# PediLEDStrip.net
KiCad netlist of a schematic drawn in EAGLE
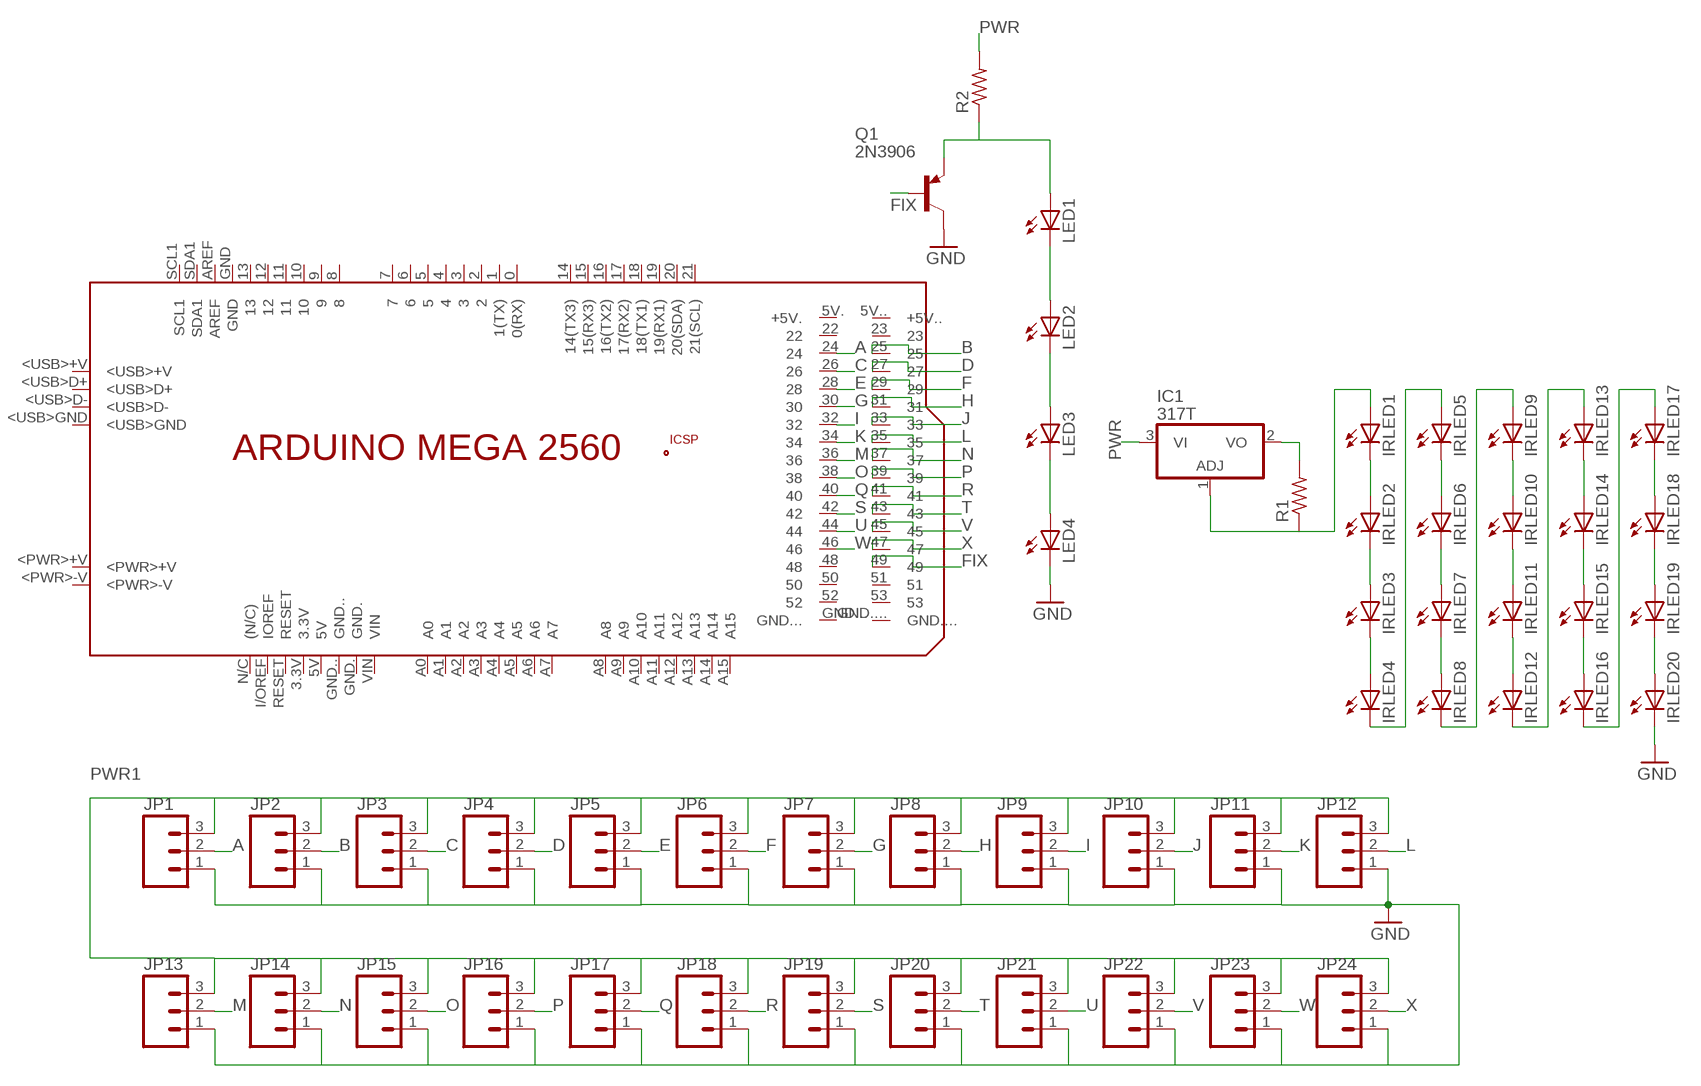
[diagram p0: schematic, sheet 1]

(export (version "E")
  (design (tool "Eeschema 10.0.6"))
  (components
    (comp (ref "IC1")
      (value "317T")
      (footprint "eagle-import:TO220H")
      (libsource (lib "eagle-import") (part "317T"))
    )
    (comp (ref "IRLED1")
      (value "LED5MM")
      (footprint "eagle-import:LED5MM")
      (libsource (lib "eagle-import") (part "LED5MM"))
    )
    (comp (ref "IRLED2")
      (value "LED5MM")
      (footprint "eagle-import:LED5MM")
      (libsource (lib "eagle-import") (part "LED5MM"))
    )
    (comp (ref "IRLED3")
      (value "LED5MM")
      (footprint "eagle-import:LED5MM")
      (libsource (lib "eagle-import") (part "LED5MM"))
    )
    (comp (ref "IRLED4")
      (value "LED5MM")
      (footprint "eagle-import:LED5MM")
      (libsource (lib "eagle-import") (part "LED5MM"))
    )
    (comp (ref "IRLED5")
      (value "LED5MM")
      (footprint "eagle-import:LED5MM")
      (libsource (lib "eagle-import") (part "LED5MM"))
    )
    (comp (ref "IRLED6")
      (value "LED5MM")
      (footprint "eagle-import:LED5MM")
      (libsource (lib "eagle-import") (part "LED5MM"))
    )
    (comp (ref "IRLED7")
      (value "LED5MM")
      (footprint "eagle-import:LED5MM")
      (libsource (lib "eagle-import") (part "LED5MM"))
    )
    (comp (ref "IRLED8")
      (value "LED5MM")
      (footprint "eagle-import:LED5MM")
      (libsource (lib "eagle-import") (part "LED5MM"))
    )
    (comp (ref "IRLED9")
      (value "LED5MM")
      (footprint "eagle-import:LED5MM")
      (libsource (lib "eagle-import") (part "LED5MM"))
    )
    (comp (ref "IRLED10")
      (value "LED5MM")
      (footprint "eagle-import:LED5MM")
      (libsource (lib "eagle-import") (part "LED5MM"))
    )
    (comp (ref "IRLED11")
      (value "LED5MM")
      (footprint "eagle-import:LED5MM")
      (libsource (lib "eagle-import") (part "LED5MM"))
    )
    (comp (ref "IRLED12")
      (value "LED5MM")
      (footprint "eagle-import:LED5MM")
      (libsource (lib "eagle-import") (part "LED5MM"))
    )
    (comp (ref "IRLED13")
      (value "LED5MM")
      (footprint "eagle-import:LED5MM")
      (libsource (lib "eagle-import") (part "LED5MM"))
    )
    (comp (ref "IRLED14")
      (value "LED5MM")
      (footprint "eagle-import:LED5MM")
      (libsource (lib "eagle-import") (part "LED5MM"))
    )
    (comp (ref "IRLED15")
      (value "LED5MM")
      (footprint "eagle-import:LED5MM")
      (libsource (lib "eagle-import") (part "LED5MM"))
    )
    (comp (ref "IRLED16")
      (value "LED5MM")
      (footprint "eagle-import:LED5MM")
      (libsource (lib "eagle-import") (part "LED5MM"))
    )
    (comp (ref "IRLED17")
      (value "LED5MM")
      (footprint "eagle-import:LED5MM")
      (libsource (lib "eagle-import") (part "LED5MM"))
    )
    (comp (ref "IRLED18")
      (value "LED5MM")
      (footprint "eagle-import:LED5MM")
      (libsource (lib "eagle-import") (part "LED5MM"))
    )
    (comp (ref "IRLED19")
      (value "LED5MM")
      (footprint "eagle-import:LED5MM")
      (libsource (lib "eagle-import") (part "LED5MM"))
    )
    (comp (ref "IRLED20")
      (value "LED5MM")
      (footprint "eagle-import:LED5MM")
      (libsource (lib "eagle-import") (part "LED5MM"))
    )
    (comp (ref "JP1")
      (value "M03PTH")
      (footprint "eagle-import:1X03")
      (libsource (lib "eagle-import") (part "M03PTH"))
    )
    (comp (ref "JP2")
      (value "M03PTH")
      (footprint "eagle-import:1X03")
      (libsource (lib "eagle-import") (part "M03PTH"))
    )
    (comp (ref "JP3")
      (value "M03PTH")
      (footprint "eagle-import:1X03")
      (libsource (lib "eagle-import") (part "M03PTH"))
    )
    (comp (ref "JP4")
      (value "M03PTH")
      (footprint "eagle-import:1X03")
      (libsource (lib "eagle-import") (part "M03PTH"))
    )
    (comp (ref "JP5")
      (value "M03PTH")
      (footprint "eagle-import:1X03")
      (libsource (lib "eagle-import") (part "M03PTH"))
    )
    (comp (ref "JP6")
      (value "M03PTH")
      (footprint "eagle-import:1X03")
      (libsource (lib "eagle-import") (part "M03PTH"))
    )
    (comp (ref "JP7")
      (value "M03PTH")
      (footprint "eagle-import:1X03")
      (libsource (lib "eagle-import") (part "M03PTH"))
    )
    (comp (ref "JP8")
      (value "M03PTH")
      (footprint "eagle-import:1X03")
      (libsource (lib "eagle-import") (part "M03PTH"))
    )
    (comp (ref "JP9")
      (value "M03PTH")
      (footprint "eagle-import:1X03")
      (libsource (lib "eagle-import") (part "M03PTH"))
    )
    (comp (ref "JP10")
      (value "M03PTH")
      (footprint "eagle-import:1X03")
      (libsource (lib "eagle-import") (part "M03PTH"))
    )
    (comp (ref "JP11")
      (value "M03PTH")
      (footprint "eagle-import:1X03")
      (libsource (lib "eagle-import") (part "M03PTH"))
    )
    (comp (ref "JP12")
      (value "M03PTH")
      (footprint "eagle-import:1X03")
      (libsource (lib "eagle-import") (part "M03PTH"))
    )
    (comp (ref "JP13")
      (value "M03PTH")
      (footprint "eagle-import:1X03")
      (libsource (lib "eagle-import") (part "M03PTH"))
    )
    (comp (ref "JP14")
      (value "M03PTH")
      (footprint "eagle-import:1X03")
      (libsource (lib "eagle-import") (part "M03PTH"))
    )
    (comp (ref "JP15")
      (value "M03PTH")
      (footprint "eagle-import:1X03")
      (libsource (lib "eagle-import") (part "M03PTH"))
    )
    (comp (ref "JP16")
      (value "M03PTH")
      (footprint "eagle-import:1X03")
      (libsource (lib "eagle-import") (part "M03PTH"))
    )
    (comp (ref "JP17")
      (value "M03PTH")
      (footprint "eagle-import:1X03")
      (libsource (lib "eagle-import") (part "M03PTH"))
    )
    (comp (ref "JP18")
      (value "M03PTH")
      (footprint "eagle-import:1X03")
      (libsource (lib "eagle-import") (part "M03PTH"))
    )
    (comp (ref "JP19")
      (value "M03PTH")
      (footprint "eagle-import:1X03")
      (libsource (lib "eagle-import") (part "M03PTH"))
    )
    (comp (ref "JP20")
      (value "M03PTH")
      (footprint "eagle-import:1X03")
      (libsource (lib "eagle-import") (part "M03PTH"))
    )
    (comp (ref "JP21")
      (value "M03PTH")
      (footprint "eagle-import:1X03")
      (libsource (lib "eagle-import") (part "M03PTH"))
    )
    (comp (ref "JP22")
      (value "M03PTH")
      (footprint "eagle-import:1X03")
      (libsource (lib "eagle-import") (part "M03PTH"))
    )
    (comp (ref "JP23")
      (value "M03PTH")
      (footprint "eagle-import:1X03")
      (libsource (lib "eagle-import") (part "M03PTH"))
    )
    (comp (ref "JP24")
      (value "M03PTH")
      (footprint "eagle-import:1X03")
      (libsource (lib "eagle-import") (part "M03PTH"))
    )
    (comp (ref "LED1")
      (value "LED5MM")
      (footprint "eagle-import:LED5MM")
      (libsource (lib "eagle-import") (part "LED5MM"))
    )
    (comp (ref "LED2")
      (value "LED5MM")
      (footprint "eagle-import:LED5MM")
      (libsource (lib "eagle-import") (part "LED5MM"))
    )
    (comp (ref "LED3")
      (value "LED5MM")
      (footprint "eagle-import:LED5MM")
      (libsource (lib "eagle-import") (part "LED5MM"))
    )
    (comp (ref "LED4")
      (value "LED5MM")
      (footprint "eagle-import:LED5MM")
      (libsource (lib "eagle-import") (part "LED5MM"))
    )
    (comp (ref "PCB1")
      (value "ARDUINO_MEGA2560")
      (footprint "eagle-import:ARDUINO_MEGA2560")
      (libsource (lib "eagle-import") (part "ARDUINO_MEGA2560"))
    )
    (comp (ref "Q1")
      (value "2N3906")
      (footprint "eagle-import:TO92")
      (libsource (lib "eagle-import") (part "2N3906"))
    )
    (comp (ref "R1")
      (value "R-US_0207/10")
      (footprint "eagle-import:0207_10")
      (libsource (lib "eagle-import") (part "R-US_0207/10"))
    )
    (comp (ref "R2")
      (value "R-US_0207/10")
      (footprint "eagle-import:0207_10")
      (libsource (lib "eagle-import") (part "R-US_0207/10"))
    )
  )
  (nets
    (net (code "1") (name "/A") (class "Default")
      (node (ref "JP1") (pin "2") (pinfunction "2_2") (pintype "passive"))
      (node (ref "PCB1") (pin "24") (pinfunction "24_24") (pintype "bidirectional"))
    )
    (net (code "2") (name "/B") (class "Default")
      (node (ref "JP2") (pin "2") (pinfunction "2_2") (pintype "passive"))
      (node (ref "PCB1") (pin "25") (pinfunction "25_25") (pintype "bidirectional"))
    )
    (net (code "3") (name "/C") (class "Default")
      (node (ref "JP3") (pin "2") (pinfunction "2_2") (pintype "passive"))
      (node (ref "PCB1") (pin "26") (pinfunction "26_26") (pintype "bidirectional"))
    )
    (net (code "4") (name "/D") (class "Default")
      (node (ref "JP4") (pin "2") (pinfunction "2_2") (pintype "passive"))
      (node (ref "PCB1") (pin "27") (pinfunction "27_27") (pintype "bidirectional"))
    )
    (net (code "5") (name "/E") (class "Default")
      (node (ref "JP5") (pin "2") (pinfunction "2_2") (pintype "passive"))
      (node (ref "PCB1") (pin "28") (pinfunction "28_28") (pintype "bidirectional"))
    )
    (net (code "6") (name "/F") (class "Default")
      (node (ref "JP6") (pin "2") (pinfunction "2_2") (pintype "passive"))
      (node (ref "PCB1") (pin "29") (pinfunction "29_29") (pintype "bidirectional"))
    )
    (net (code "7") (name "/FIX") (class "Default")
      (node (ref "PCB1") (pin "49") (pinfunction "49_49") (pintype "bidirectional"))
      (node (ref "Q1") (pin "2") (pinfunction "B_2") (pintype "passive"))
    )
    (net (code "8") (name "/G") (class "Default")
      (node (ref "JP7") (pin "2") (pinfunction "2_2") (pintype "passive"))
      (node (ref "PCB1") (pin "30") (pinfunction "30_30") (pintype "bidirectional"))
    )
    (net (code "9") (name "/H") (class "Default")
      (node (ref "JP8") (pin "2") (pinfunction "2_2") (pintype "passive"))
      (node (ref "PCB1") (pin "31") (pinfunction "31_31") (pintype "bidirectional"))
    )
    (net (code "10") (name "/I") (class "Default")
      (node (ref "JP9") (pin "2") (pinfunction "2_2") (pintype "passive"))
      (node (ref "PCB1") (pin "32") (pinfunction "32_32") (pintype "bidirectional"))
    )
    (net (code "11") (name "/J") (class "Default")
      (node (ref "JP10") (pin "2") (pinfunction "2_2") (pintype "passive"))
      (node (ref "PCB1") (pin "33") (pinfunction "33_33") (pintype "bidirectional"))
    )
    (net (code "12") (name "/K") (class "Default")
      (node (ref "JP11") (pin "2") (pinfunction "2_2") (pintype "passive"))
      (node (ref "PCB1") (pin "34") (pinfunction "34_34") (pintype "bidirectional"))
    )
    (net (code "13") (name "/L") (class "Default")
      (node (ref "JP12") (pin "2") (pinfunction "2_2") (pintype "passive"))
      (node (ref "PCB1") (pin "35") (pinfunction "35_35") (pintype "bidirectional"))
    )
    (net (code "14") (name "/M") (class "Default")
      (node (ref "JP13") (pin "2") (pinfunction "2_2") (pintype "passive"))
      (node (ref "PCB1") (pin "36") (pinfunction "36_36") (pintype "bidirectional"))
    )
    (net (code "15") (name "/N") (class "Default")
      (node (ref "JP14") (pin "2") (pinfunction "2_2") (pintype "passive"))
      (node (ref "PCB1") (pin "37") (pinfunction "37_37") (pintype "bidirectional"))
    )
    (net (code "16") (name "/O") (class "Default")
      (node (ref "JP15") (pin "2") (pinfunction "2_2") (pintype "passive"))
      (node (ref "PCB1") (pin "38") (pinfunction "38_38") (pintype "bidirectional"))
    )
    (net (code "17") (name "/P") (class "Default")
      (node (ref "JP16") (pin "2") (pinfunction "2_2") (pintype "passive"))
      (node (ref "PCB1") (pin "39") (pinfunction "39_39") (pintype "bidirectional"))
    )
    (net (code "18") (name "/PWR") (class "Default")
      (node (ref "IC1") (pin "3") (pinfunction "VI_3") (pintype "input"))
      (node (ref "R2") (pin "2") (pinfunction "2_2") (pintype "passive"))
    )
    (net (code "19") (name "/PWR1") (class "Default")
      (node (ref "JP1") (pin "3") (pinfunction "3_3") (pintype "passive"))
      (node (ref "JP10") (pin "3") (pinfunction "3_3") (pintype "passive"))
      (node (ref "JP11") (pin "3") (pinfunction "3_3") (pintype "passive"))
      (node (ref "JP12") (pin "3") (pinfunction "3_3") (pintype "passive"))
      (node (ref "JP13") (pin "3") (pinfunction "3_3") (pintype "passive"))
      (node (ref "JP14") (pin "3") (pinfunction "3_3") (pintype "passive"))
      (node (ref "JP15") (pin "3") (pinfunction "3_3") (pintype "passive"))
      (node (ref "JP16") (pin "3") (pinfunction "3_3") (pintype "passive"))
      (node (ref "JP17") (pin "3") (pinfunction "3_3") (pintype "passive"))
      (node (ref "JP18") (pin "3") (pinfunction "3_3") (pintype "passive"))
      (node (ref "JP19") (pin "3") (pinfunction "3_3") (pintype "passive"))
      (node (ref "JP2") (pin "3") (pinfunction "3_3") (pintype "passive"))
      (node (ref "JP20") (pin "3") (pinfunction "3_3") (pintype "passive"))
      (node (ref "JP21") (pin "3") (pinfunction "3_3") (pintype "passive"))
      (node (ref "JP22") (pin "3") (pinfunction "3_3") (pintype "passive"))
      (node (ref "JP23") (pin "3") (pinfunction "3_3") (pintype "passive"))
      (node (ref "JP24") (pin "3") (pinfunction "3_3") (pintype "passive"))
      (node (ref "JP3") (pin "3") (pinfunction "3_3") (pintype "passive"))
      (node (ref "JP4") (pin "3") (pinfunction "3_3") (pintype "passive"))
      (node (ref "JP5") (pin "3") (pinfunction "3_3") (pintype "passive"))
      (node (ref "JP6") (pin "3") (pinfunction "3_3") (pintype "passive"))
      (node (ref "JP7") (pin "3") (pinfunction "3_3") (pintype "passive"))
      (node (ref "JP8") (pin "3") (pinfunction "3_3") (pintype "passive"))
      (node (ref "JP9") (pin "3") (pinfunction "3_3") (pintype "passive"))
    )
    (net (code "20") (name "/Q") (class "Default")
      (node (ref "JP17") (pin "2") (pinfunction "2_2") (pintype "passive"))
      (node (ref "PCB1") (pin "40") (pinfunction "40_40") (pintype "bidirectional"))
    )
    (net (code "21") (name "/R") (class "Default")
      (node (ref "JP18") (pin "2") (pinfunction "2_2") (pintype "passive"))
      (node (ref "PCB1") (pin "41") (pinfunction "41_41") (pintype "bidirectional"))
    )
    (net (code "22") (name "/S") (class "Default")
      (node (ref "JP19") (pin "2") (pinfunction "2_2") (pintype "passive"))
      (node (ref "PCB1") (pin "42") (pinfunction "42_42") (pintype "bidirectional"))
    )
    (net (code "23") (name "/T") (class "Default")
      (node (ref "JP20") (pin "2") (pinfunction "2_2") (pintype "passive"))
      (node (ref "PCB1") (pin "43") (pinfunction "43_43") (pintype "bidirectional"))
    )
    (net (code "24") (name "/U") (class "Default")
      (node (ref "JP21") (pin "2") (pinfunction "2_2") (pintype "passive"))
      (node (ref "PCB1") (pin "44") (pinfunction "44_44") (pintype "bidirectional"))
    )
    (net (code "25") (name "/V") (class "Default")
      (node (ref "JP22") (pin "2") (pinfunction "2_2") (pintype "passive"))
      (node (ref "PCB1") (pin "45") (pinfunction "45_45") (pintype "bidirectional"))
    )
    (net (code "26") (name "/W") (class "Default")
      (node (ref "JP23") (pin "2") (pinfunction "2_2") (pintype "passive"))
      (node (ref "PCB1") (pin "46") (pinfunction "46_46") (pintype "bidirectional"))
    )
    (net (code "27") (name "/X") (class "Default")
      (node (ref "JP24") (pin "2") (pinfunction "2_2") (pintype "passive"))
      (node (ref "PCB1") (pin "47") (pinfunction "47_47") (pintype "bidirectional"))
    )
    (net (code "28") (name "GND") (class "Default")
      (node (ref "IRLED20") (pin "K") (pinfunction "C_K") (pintype "passive"))
      (node (ref "JP1") (pin "1") (pinfunction "1_1") (pintype "passive"))
      (node (ref "JP10") (pin "1") (pinfunction "1_1") (pintype "passive"))
      (node (ref "JP11") (pin "1") (pinfunction "1_1") (pintype "passive"))
      (node (ref "JP12") (pin "1") (pinfunction "1_1") (pintype "passive"))
      (node (ref "JP13") (pin "1") (pinfunction "1_1") (pintype "passive"))
      (node (ref "JP14") (pin "1") (pinfunction "1_1") (pintype "passive"))
      (node (ref "JP15") (pin "1") (pinfunction "1_1") (pintype "passive"))
      (node (ref "JP16") (pin "1") (pinfunction "1_1") (pintype "passive"))
      (node (ref "JP17") (pin "1") (pinfunction "1_1") (pintype "passive"))
      (node (ref "JP18") (pin "1") (pinfunction "1_1") (pintype "passive"))
      (node (ref "JP19") (pin "1") (pinfunction "1_1") (pintype "passive"))
      (node (ref "JP2") (pin "1") (pinfunction "1_1") (pintype "passive"))
      (node (ref "JP20") (pin "1") (pinfunction "1_1") (pintype "passive"))
      (node (ref "JP21") (pin "1") (pinfunction "1_1") (pintype "passive"))
      (node (ref "JP22") (pin "1") (pinfunction "1_1") (pintype "passive"))
      (node (ref "JP23") (pin "1") (pinfunction "1_1") (pintype "passive"))
      (node (ref "JP24") (pin "1") (pinfunction "1_1") (pintype "passive"))
      (node (ref "JP3") (pin "1") (pinfunction "1_1") (pintype "passive"))
      (node (ref "JP4") (pin "1") (pinfunction "1_1") (pintype "passive"))
      (node (ref "JP5") (pin "1") (pinfunction "1_1") (pintype "passive"))
      (node (ref "JP6") (pin "1") (pinfunction "1_1") (pintype "passive"))
      (node (ref "JP7") (pin "1") (pinfunction "1_1") (pintype "passive"))
      (node (ref "JP8") (pin "1") (pinfunction "1_1") (pintype "passive"))
      (node (ref "JP9") (pin "1") (pinfunction "1_1") (pintype "passive"))
      (node (ref "LED4") (pin "K") (pinfunction "C_K") (pintype "passive"))
      (node (ref "Q1") (pin "1") (pinfunction "C_1") (pintype "passive"))
    )
    (net (code "29") (name "Net-(IC1-ADJ)") (class "Default")
      (node (ref "IC1") (pin "1") (pinfunction "ADJ_1") (pintype "input"))
      (node (ref "IRLED1") (pin "A") (pinfunction "A_A") (pintype "passive"))
      (node (ref "R1") (pin "1") (pinfunction "1_1") (pintype "passive"))
    )
    (net (code "30") (name "Net-(IC1-VO)") (class "Default")
      (node (ref "IC1") (pin "2") (pinfunction "VO_2") (pintype "passive"))
      (node (ref "R1") (pin "2") (pinfunction "2_2") (pintype "passive"))
    )
    (net (code "31") (name "Net-(IRLED1-C)") (class "Default")
      (node (ref "IRLED1") (pin "K") (pinfunction "C_K") (pintype "passive"))
      (node (ref "IRLED2") (pin "A") (pinfunction "A_A") (pintype "passive"))
    )
    (net (code "32") (name "Net-(IRLED2-C)") (class "Default")
      (node (ref "IRLED2") (pin "K") (pinfunction "C_K") (pintype "passive"))
      (node (ref "IRLED3") (pin "A") (pinfunction "A_A") (pintype "passive"))
    )
    (net (code "33") (name "Net-(IRLED3-C)") (class "Default")
      (node (ref "IRLED3") (pin "K") (pinfunction "C_K") (pintype "passive"))
      (node (ref "IRLED4") (pin "A") (pinfunction "A_A") (pintype "passive"))
    )
    (net (code "34") (name "Net-(IRLED4-C)") (class "Default")
      (node (ref "IRLED4") (pin "K") (pinfunction "C_K") (pintype "passive"))
      (node (ref "IRLED5") (pin "A") (pinfunction "A_A") (pintype "passive"))
    )
    (net (code "35") (name "Net-(IRLED5-C)") (class "Default")
      (node (ref "IRLED5") (pin "K") (pinfunction "C_K") (pintype "passive"))
      (node (ref "IRLED6") (pin "A") (pinfunction "A_A") (pintype "passive"))
    )
    (net (code "36") (name "Net-(IRLED6-C)") (class "Default")
      (node (ref "IRLED6") (pin "K") (pinfunction "C_K") (pintype "passive"))
      (node (ref "IRLED7") (pin "A") (pinfunction "A_A") (pintype "passive"))
    )
    (net (code "37") (name "Net-(IRLED7-C)") (class "Default")
      (node (ref "IRLED7") (pin "K") (pinfunction "C_K") (pintype "passive"))
      (node (ref "IRLED8") (pin "A") (pinfunction "A_A") (pintype "passive"))
    )
    (net (code "38") (name "Net-(IRLED8-C)") (class "Default")
      (node (ref "IRLED8") (pin "K") (pinfunction "C_K") (pintype "passive"))
      (node (ref "IRLED9") (pin "A") (pinfunction "A_A") (pintype "passive"))
    )
    (net (code "39") (name "Net-(IRLED9-C)") (class "Default")
      (node (ref "IRLED10") (pin "A") (pinfunction "A_A") (pintype "passive"))
      (node (ref "IRLED9") (pin "K") (pinfunction "C_K") (pintype "passive"))
    )
    (net (code "40") (name "Net-(IRLED10-C)") (class "Default")
      (node (ref "IRLED10") (pin "K") (pinfunction "C_K") (pintype "passive"))
      (node (ref "IRLED11") (pin "A") (pinfunction "A_A") (pintype "passive"))
    )
    (net (code "41") (name "Net-(IRLED11-C)") (class "Default")
      (node (ref "IRLED11") (pin "K") (pinfunction "C_K") (pintype "passive"))
      (node (ref "IRLED12") (pin "A") (pinfunction "A_A") (pintype "passive"))
    )
    (net (code "42") (name "Net-(IRLED12-C)") (class "Default")
      (node (ref "IRLED12") (pin "K") (pinfunction "C_K") (pintype "passive"))
      (node (ref "IRLED13") (pin "A") (pinfunction "A_A") (pintype "passive"))
    )
    (net (code "43") (name "Net-(IRLED13-C)") (class "Default")
      (node (ref "IRLED13") (pin "K") (pinfunction "C_K") (pintype "passive"))
      (node (ref "IRLED14") (pin "A") (pinfunction "A_A") (pintype "passive"))
    )
    (net (code "44") (name "Net-(IRLED14-C)") (class "Default")
      (node (ref "IRLED14") (pin "K") (pinfunction "C_K") (pintype "passive"))
      (node (ref "IRLED15") (pin "A") (pinfunction "A_A") (pintype "passive"))
    )
    (net (code "45") (name "Net-(IRLED15-C)") (class "Default")
      (node (ref "IRLED15") (pin "K") (pinfunction "C_K") (pintype "passive"))
      (node (ref "IRLED16") (pin "A") (pinfunction "A_A") (pintype "passive"))
    )
    (net (code "46") (name "Net-(IRLED16-C)") (class "Default")
      (node (ref "IRLED16") (pin "K") (pinfunction "C_K") (pintype "passive"))
      (node (ref "IRLED17") (pin "A") (pinfunction "A_A") (pintype "passive"))
    )
    (net (code "47") (name "Net-(IRLED17-C)") (class "Default")
      (node (ref "IRLED17") (pin "K") (pinfunction "C_K") (pintype "passive"))
      (node (ref "IRLED18") (pin "A") (pinfunction "A_A") (pintype "passive"))
    )
    (net (code "48") (name "Net-(IRLED18-C)") (class "Default")
      (node (ref "IRLED18") (pin "K") (pinfunction "C_K") (pintype "passive"))
      (node (ref "IRLED19") (pin "A") (pinfunction "A_A") (pintype "passive"))
    )
    (net (code "49") (name "Net-(IRLED19-C)") (class "Default")
      (node (ref "IRLED19") (pin "K") (pinfunction "C_K") (pintype "passive"))
      (node (ref "IRLED20") (pin "A") (pinfunction "A_A") (pintype "passive"))
    )
    (net (code "50") (name "Net-(LED1-C)") (class "Default")
      (node (ref "LED1") (pin "K") (pinfunction "C_K") (pintype "passive"))
      (node (ref "LED2") (pin "A") (pinfunction "A_A") (pintype "passive"))
    )
    (net (code "51") (name "Net-(LED2-C)") (class "Default")
      (node (ref "LED2") (pin "K") (pinfunction "C_K") (pintype "passive"))
      (node (ref "LED3") (pin "A") (pinfunction "A_A") (pintype "passive"))
    )
    (net (code "52") (name "Net-(LED3-C)") (class "Default")
      (node (ref "LED3") (pin "K") (pinfunction "C_K") (pintype "passive"))
      (node (ref "LED4") (pin "A") (pinfunction "A_A") (pintype "passive"))
    )
    (net (code "53") (name "Net-(Q1-E)") (class "Default")
      (node (ref "LED1") (pin "A") (pinfunction "A_A") (pintype "passive"))
      (node (ref "Q1") (pin "3") (pinfunction "E_3") (pintype "passive"))
      (node (ref "R2") (pin "1") (pinfunction "1_1") (pintype "passive"))
    )
    (net (code "54") (name "unconnected-(PCB1-(N{slash}C)-PadN{slash}C)") (class "Default")
      (node (ref "PCB1") (pin "N/C") (pinfunction "(N/C)_N/C") (pintype "bidirectional"))
    )
    (net (code "55") (name "unconnected-(PCB1-+5V.-Pad5V.)") (class "Default")
      (node (ref "PCB1") (pin "5V.") (pinfunction "+5V._5V.") (pintype "bidirectional"))
    )
    (net (code "56") (name "unconnected-(PCB1-+5V..-Pad5V..)") (class "Default")
      (node (ref "PCB1") (pin "5V..") (pinfunction "+5V.._5V..") (pintype "bidirectional"))
    )
    (net (code "57") (name "unconnected-(PCB1-0(RX)-Pad0)") (class "Default")
      (node (ref "PCB1") (pin "0") (pinfunction "0(RX)_0") (pintype "bidirectional"))
    )
    (net (code "58") (name "unconnected-(PCB1-1(TX)-Pad1)") (class "Default")
      (node (ref "PCB1") (pin "1") (pinfunction "1(TX)_1") (pintype "bidirectional"))
    )
    (net (code "59") (name "unconnected-(PCB1-14(TX3)-Pad14)") (class "Default")
      (node (ref "PCB1") (pin "14") (pinfunction "14(TX3)_14") (pintype "bidirectional"))
    )
    (net (code "60") (name "unconnected-(PCB1-15(RX3)-Pad15)") (class "Default")
      (node (ref "PCB1") (pin "15") (pinfunction "15(RX3)_15") (pintype "bidirectional"))
    )
    (net (code "61") (name "unconnected-(PCB1-16(TX2)-Pad16)") (class "Default")
      (node (ref "PCB1") (pin "16") (pinfunction "16(TX2)_16") (pintype "bidirectional"))
    )
    (net (code "62") (name "unconnected-(PCB1-17(RX2)-Pad17)") (class "Default")
      (node (ref "PCB1") (pin "17") (pinfunction "17(RX2)_17") (pintype "bidirectional"))
    )
    (net (code "63") (name "unconnected-(PCB1-18(TX1)-Pad18)") (class "Default")
      (node (ref "PCB1") (pin "18") (pinfunction "18(TX1)_18") (pintype "bidirectional"))
    )
    (net (code "64") (name "unconnected-(PCB1-19(RX1)-Pad19)") (class "Default")
      (node (ref "PCB1") (pin "19") (pinfunction "19(RX1)_19") (pintype "bidirectional"))
    )
    (net (code "65") (name "unconnected-(PCB1-20(SDA)-Pad20)") (class "Default")
      (node (ref "PCB1") (pin "20") (pinfunction "20(SDA)_20") (pintype "bidirectional"))
    )
    (net (code "66") (name "unconnected-(PCB1-21(SCL)-Pad21)") (class "Default")
      (node (ref "PCB1") (pin "21") (pinfunction "21(SCL)_21") (pintype "bidirectional"))
    )
    (net (code "67") (name "unconnected-(PCB1-IOREF-PadI{slash}OREF)") (class "Default")
      (node (ref "PCB1") (pin "I/OREF") (pinfunction "IOREF_I/OREF") (pintype "bidirectional"))
    )
    (net (code "68") (name "unconnected-(PCB1-Pad+5V_)") (class "Default")
      (node (ref "PCB1") (pin "+5V_") (pinfunction "+5V__+5V_") (pintype "bidirectional"))
    )
    (net (code "69") (name "unconnected-(PCB1-Pad2)") (class "Default")
      (node (ref "PCB1") (pin "2") (pinfunction "2_2") (pintype "bidirectional"))
    )
    (net (code "70") (name "unconnected-(PCB1-Pad3)") (class "Default")
      (node (ref "PCB1") (pin "3") (pinfunction "3_3") (pintype "bidirectional"))
    )
    (net (code "71") (name "unconnected-(PCB1-Pad3.3V)") (class "Default")
      (node (ref "PCB1") (pin "3.3V") (pinfunction "3.3V_3.3V") (pintype "bidirectional"))
    )
    (net (code "72") (name "unconnected-(PCB1-Pad4)") (class "Default")
      (node (ref "PCB1") (pin "4") (pinfunction "4_4") (pintype "bidirectional"))
    )
    (net (code "73") (name "unconnected-(PCB1-Pad5)") (class "Default")
      (node (ref "PCB1") (pin "5") (pinfunction "5_5") (pintype "bidirectional"))
    )
    (net (code "74") (name "unconnected-(PCB1-Pad5V)") (class "Default")
      (node (ref "PCB1") (pin "5V") (pinfunction "5V_5V") (pintype "bidirectional"))
    )
    (net (code "75") (name "unconnected-(PCB1-Pad6)") (class "Default")
      (node (ref "PCB1") (pin "6") (pinfunction "6_6") (pintype "bidirectional"))
    )
    (net (code "76") (name "unconnected-(PCB1-Pad7)") (class "Default")
      (node (ref "PCB1") (pin "7") (pinfunction "7_7") (pintype "bidirectional"))
    )
    (net (code "77") (name "unconnected-(PCB1-Pad8)") (class "Default")
      (node (ref "PCB1") (pin "8") (pinfunction "8_8") (pintype "bidirectional"))
    )
    (net (code "78") (name "unconnected-(PCB1-Pad9)") (class "Default")
      (node (ref "PCB1") (pin "9") (pinfunction "9_9") (pintype "bidirectional"))
    )
    (net (code "79") (name "unconnected-(PCB1-Pad10)") (class "Default")
      (node (ref "PCB1") (pin "10") (pinfunction "10_10") (pintype "bidirectional"))
    )
    (net (code "80") (name "unconnected-(PCB1-Pad11)") (class "Default")
      (node (ref "PCB1") (pin "11") (pinfunction "11_11") (pintype "bidirectional"))
    )
    (net (code "81") (name "unconnected-(PCB1-Pad12)") (class "Default")
      (node (ref "PCB1") (pin "12") (pinfunction "12_12") (pintype "bidirectional"))
    )
    (net (code "82") (name "unconnected-(PCB1-Pad13)") (class "Default")
      (node (ref "PCB1") (pin "13") (pinfunction "13_13") (pintype "bidirectional"))
    )
    (net (code "83") (name "unconnected-(PCB1-Pad22)") (class "Default")
      (node (ref "PCB1") (pin "22") (pinfunction "22_22") (pintype "bidirectional"))
    )
    (net (code "84") (name "unconnected-(PCB1-Pad23)") (class "Default")
      (node (ref "PCB1") (pin "23") (pinfunction "23_23") (pintype "bidirectional"))
    )
    (net (code "85") (name "unconnected-(PCB1-Pad48)") (class "Default")
      (node (ref "PCB1") (pin "48") (pinfunction "48_48") (pintype "bidirectional"))
    )
    (net (code "86") (name "unconnected-(PCB1-Pad50)") (class "Default")
      (node (ref "PCB1") (pin "50") (pinfunction "50_50") (pintype "bidirectional"))
    )
    (net (code "87") (name "unconnected-(PCB1-Pad51)") (class "Default")
      (node (ref "PCB1") (pin "51") (pinfunction "51_51") (pintype "bidirectional"))
    )
    (net (code "88") (name "unconnected-(PCB1-Pad52)") (class "Default")
      (node (ref "PCB1") (pin "52") (pinfunction "52_52") (pintype "bidirectional"))
    )
    (net (code "89") (name "unconnected-(PCB1-Pad53)") (class "Default")
      (node (ref "PCB1") (pin "53") (pinfunction "53_53") (pintype "bidirectional"))
    )
    (net (code "90") (name "unconnected-(PCB1-Pad<PWR>+V)") (class "Default")
      (node (ref "PCB1") (pin "<PWR>+V") (pinfunction "<PWR>+V_<PWR>+V") (pintype "no_connect"))
    )
    (net (code "91") (name "unconnected-(PCB1-Pad<PWR>-V)") (class "Default")
      (node (ref "PCB1") (pin "<PWR>-V") (pinfunction "<PWR>-V_<PWR>-V") (pintype "no_connect"))
    )
    (net (code "92") (name "unconnected-(PCB1-Pad<USB>+V)") (class "Default")
      (node (ref "PCB1") (pin "<USB>+V") (pinfunction "<USB>+V_<USB>+V") (pintype "no_connect"))
    )
    (net (code "93") (name "unconnected-(PCB1-Pad<USB>D+)") (class "Default")
      (node (ref "PCB1") (pin "<USB>D+") (pinfunction "<USB>D+_<USB>D+") (pintype "no_connect"))
    )
    (net (code "94") (name "unconnected-(PCB1-Pad<USB>D-)") (class "Default")
      (node (ref "PCB1") (pin "<USB>D-") (pinfunction "<USB>D-_<USB>D-") (pintype "no_connect"))
    )
    (net (code "95") (name "unconnected-(PCB1-Pad<USB>GND)") (class "Default")
      (node (ref "PCB1") (pin "<USB>GND") (pinfunction "<USB>GND_<USB>GND") (pintype "no_connect"))
    )
    (net (code "96") (name "unconnected-(PCB1-PadA0)") (class "Default")
      (node (ref "PCB1") (pin "A0") (pinfunction "A0_A0") (pintype "bidirectional"))
    )
    (net (code "97") (name "unconnected-(PCB1-PadA1)") (class "Default")
      (node (ref "PCB1") (pin "A1") (pinfunction "A1_A1") (pintype "bidirectional"))
    )
    (net (code "98") (name "unconnected-(PCB1-PadA2)") (class "Default")
      (node (ref "PCB1") (pin "A2") (pinfunction "A2_A2") (pintype "bidirectional"))
    )
    (net (code "99") (name "unconnected-(PCB1-PadA3)") (class "Default")
      (node (ref "PCB1") (pin "A3") (pinfunction "A3_A3") (pintype "bidirectional"))
    )
    (net (code "100") (name "unconnected-(PCB1-PadA4)") (class "Default")
      (node (ref "PCB1") (pin "A4") (pinfunction "A4_A4") (pintype "bidirectional"))
    )
    (net (code "101") (name "unconnected-(PCB1-PadA5)") (class "Default")
      (node (ref "PCB1") (pin "A5") (pinfunction "A5_A5") (pintype "bidirectional"))
    )
    (net (code "102") (name "unconnected-(PCB1-PadA6)") (class "Default")
      (node (ref "PCB1") (pin "A6") (pinfunction "A6_A6") (pintype "bidirectional"))
    )
    (net (code "103") (name "unconnected-(PCB1-PadA7)") (class "Default")
      (node (ref "PCB1") (pin "A7") (pinfunction "A7_A7") (pintype "bidirectional"))
    )
    (net (code "104") (name "unconnected-(PCB1-PadA8)") (class "Default")
      (node (ref "PCB1") (pin "A8") (pinfunction "A8_A8") (pintype "bidirectional"))
    )
    (net (code "105") (name "unconnected-(PCB1-PadA9)") (class "Default")
      (node (ref "PCB1") (pin "A9") (pinfunction "A9_A9") (pintype "bidirectional"))
    )
    (net (code "106") (name "unconnected-(PCB1-PadA10)") (class "Default")
      (node (ref "PCB1") (pin "A10") (pinfunction "A10_A10") (pintype "bidirectional"))
    )
    (net (code "107") (name "unconnected-(PCB1-PadA11)") (class "Default")
      (node (ref "PCB1") (pin "A11") (pinfunction "A11_A11") (pintype "bidirectional"))
    )
    (net (code "108") (name "unconnected-(PCB1-PadA12)") (class "Default")
      (node (ref "PCB1") (pin "A12") (pinfunction "A12_A12") (pintype "bidirectional"))
    )
    (net (code "109") (name "unconnected-(PCB1-PadA13)") (class "Default")
      (node (ref "PCB1") (pin "A13") (pinfunction "A13_A13") (pintype "bidirectional"))
    )
    (net (code "110") (name "unconnected-(PCB1-PadA14)") (class "Default")
      (node (ref "PCB1") (pin "A14") (pinfunction "A14_A14") (pintype "bidirectional"))
    )
    (net (code "111") (name "unconnected-(PCB1-PadA15)") (class "Default")
      (node (ref "PCB1") (pin "A15") (pinfunction "A15_A15") (pintype "bidirectional"))
    )
    (net (code "112") (name "unconnected-(PCB1-PadAREF)") (class "Default")
      (node (ref "PCB1") (pin "AREF") (pinfunction "AREF_AREF") (pintype "bidirectional"))
    )
    (net (code "113") (name "unconnected-(PCB1-PadGND)") (class "Default")
      (node (ref "PCB1") (pin "GND") (pinfunction "GND_GND") (pintype "bidirectional"))
    )
    (net (code "114") (name "unconnected-(PCB1-PadGND.)") (class "Default")
      (node (ref "PCB1") (pin "GND.") (pinfunction "GND._GND.") (pintype "bidirectional"))
    )
    (net (code "115") (name "unconnected-(PCB1-PadGND..)") (class "Default")
      (node (ref "PCB1") (pin "GND..") (pinfunction "GND.._GND..") (pintype "bidirectional"))
    )
    (net (code "116") (name "unconnected-(PCB1-PadGND...)") (class "Default")
      (node (ref "PCB1") (pin "GND...") (pinfunction "GND..._GND...") (pintype "bidirectional"))
    )
    (net (code "117") (name "unconnected-(PCB1-PadGND....)") (class "Default")
      (node (ref "PCB1") (pin "GND....") (pinfunction "GND...._GND....") (pintype "bidirectional"))
    )
    (net (code "118") (name "unconnected-(PCB1-PadGND__)") (class "Default")
      (node (ref "PCB1") (pin "GND__") (pinfunction "GND___GND__") (pintype "bidirectional"))
    )
    (net (code "119") (name "unconnected-(PCB1-PadMISO)") (class "Default")
      (node (ref "PCB1") (pin "MISO") (pinfunction "MISO_MISO") (pintype "bidirectional"))
    )
    (net (code "120") (name "unconnected-(PCB1-PadMOSI)") (class "Default")
      (node (ref "PCB1") (pin "MOSI") (pinfunction "MOSI_MOSI") (pintype "bidirectional"))
    )
    (net (code "121") (name "unconnected-(PCB1-PadRESET)") (class "Default")
      (node (ref "PCB1") (pin "RESET") (pinfunction "RESET_RESET") (pintype "bidirectional"))
    )
    (net (code "122") (name "unconnected-(PCB1-PadRESET.)") (class "Default")
      (node (ref "PCB1") (pin "RESET.") (pinfunction "RESET._RESET.") (pintype "bidirectional"))
    )
    (net (code "123") (name "unconnected-(PCB1-PadSCK)") (class "Default")
      (node (ref "PCB1") (pin "SCK") (pinfunction "SCK_SCK") (pintype "bidirectional"))
    )
    (net (code "124") (name "unconnected-(PCB1-PadSCL1)") (class "Default")
      (node (ref "PCB1") (pin "SCL1") (pinfunction "SCL1_SCL1") (pintype "bidirectional"))
    )
    (net (code "125") (name "unconnected-(PCB1-PadSDA1)") (class "Default")
      (node (ref "PCB1") (pin "SDA1") (pinfunction "SDA1_SDA1") (pintype "bidirectional"))
    )
    (net (code "126") (name "unconnected-(PCB1-PadVIN)") (class "Default")
      (node (ref "PCB1") (pin "VIN") (pinfunction "VIN_VIN") (pintype "bidirectional"))
    )
  )
)
